# RelayOnAStick.net
KiCad netlist of a schematic drawn in EAGLE
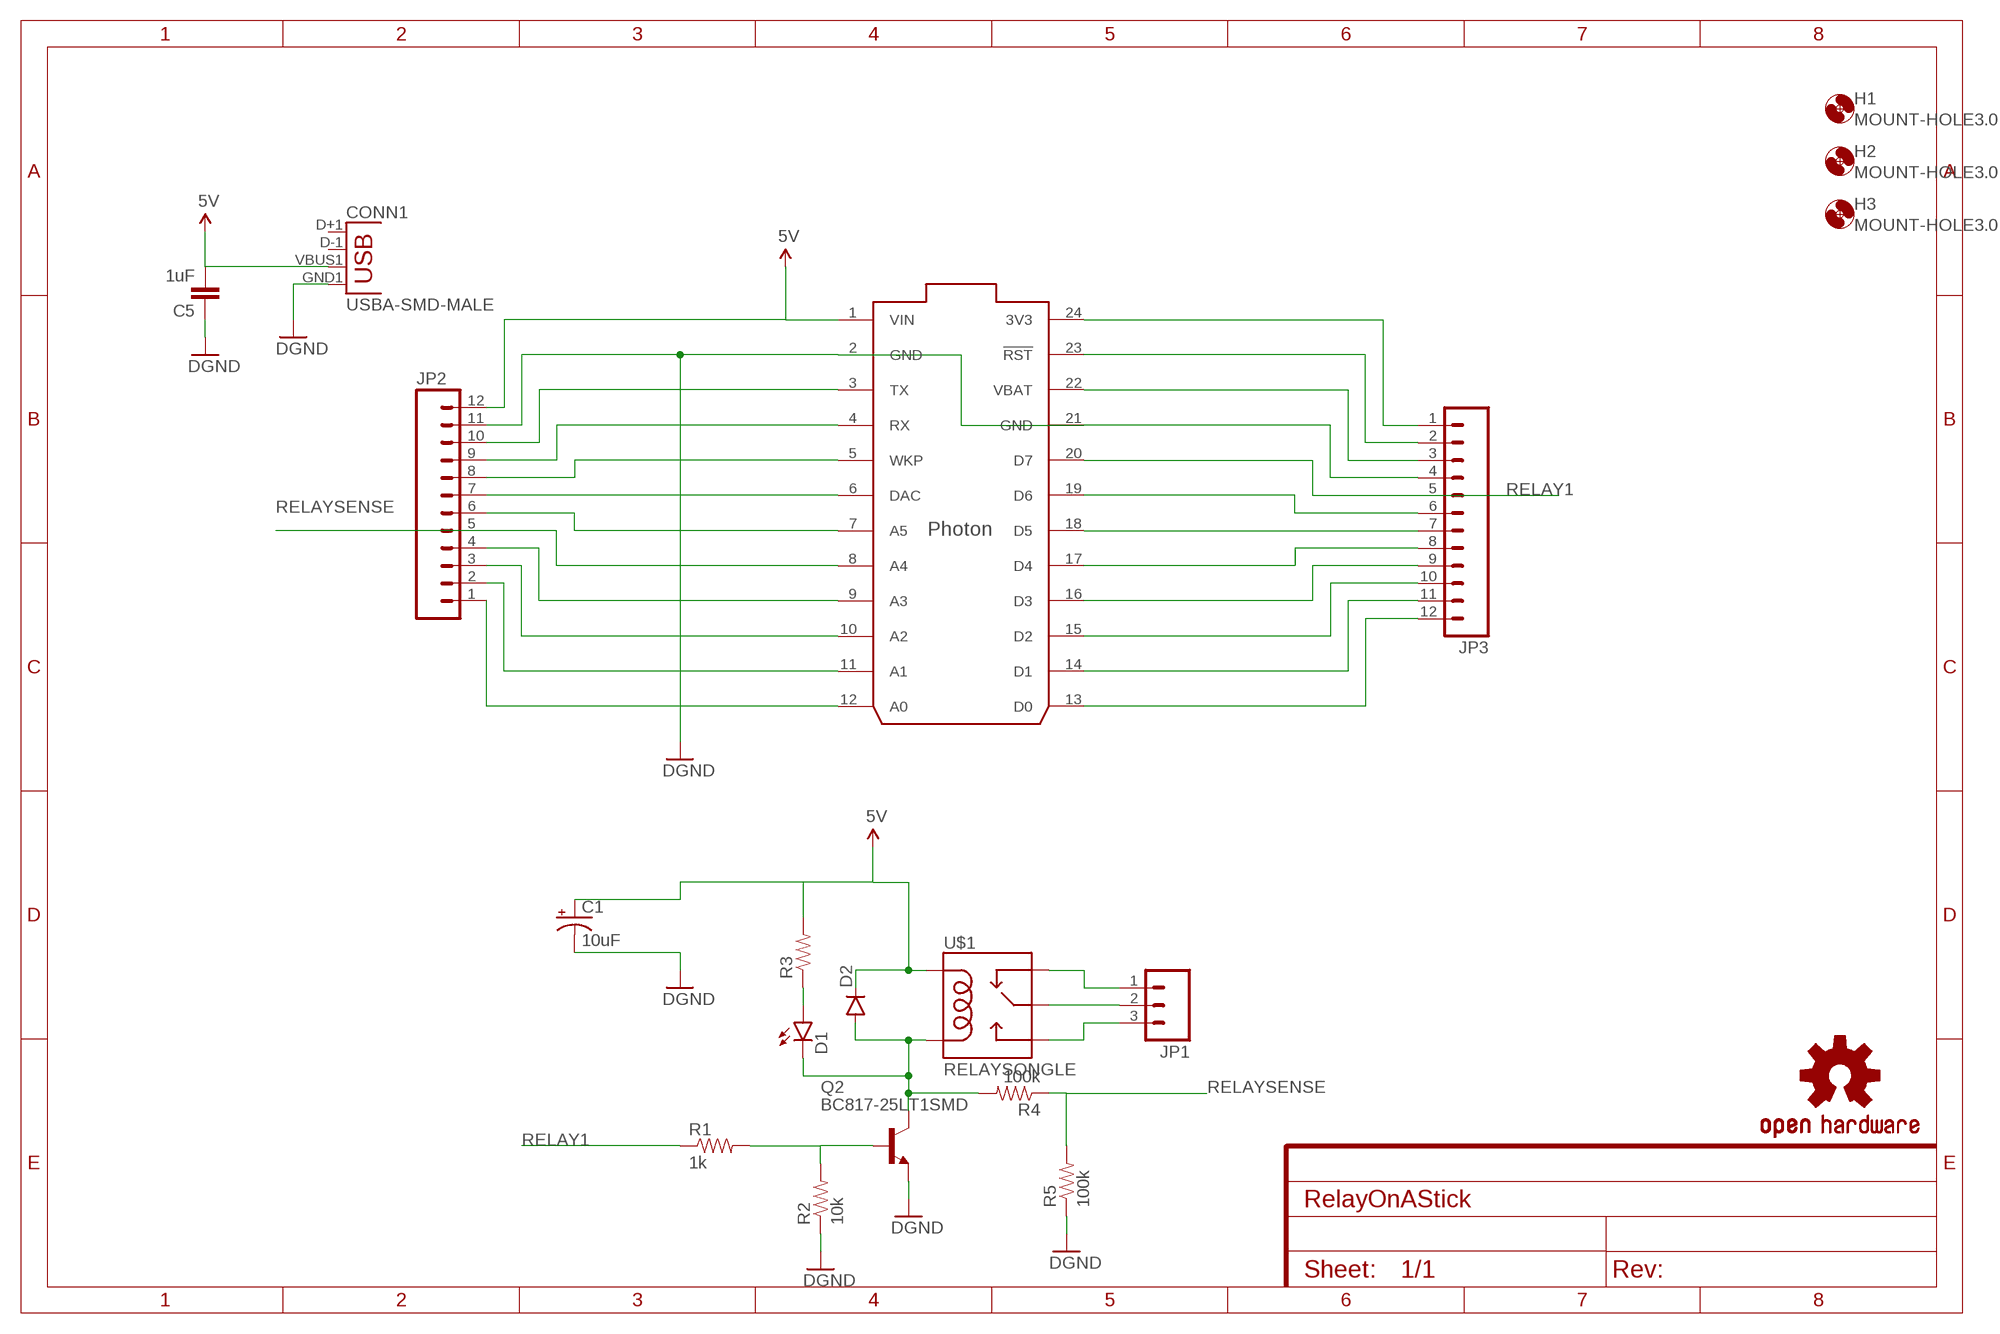
[diagram p0: schematic, sheet 1]

(export (version "E")
  (design (tool "Eeschema 10.0.6"))
  (components
    (comp (ref "C1")
      (value "10uF")
      (footprint "eagle-import:EIA3216")
      (libsource (lib "eagle-import") (part "10UF-16V-10%(TANT)"))
    )
    (comp (ref "C5")
      (value "1uF")
      (footprint "eagle-import:0805")
      (libsource (lib "eagle-import") (part "CAP0805"))
    )
    (comp (ref "CONN1")
      (value "USBA-SMD-MALE")
      (footprint "eagle-import:USB-A-SMT-MALE")
      (libsource (lib "eagle-import") (part "USBA-SMD-MALE"))
    )
    (comp (ref "D1")
      (value "LED1206")
      (footprint "eagle-import:LED-1206")
      (libsource (lib "eagle-import") (part "LED1206"))
    )
    (comp (ref "D2")
      (value "DIODESMA")
      (footprint "eagle-import:SMA-DIODE")
      (libsource (lib "eagle-import") (part "DIODESMA"))
    )
    (comp (ref "H1")
      (value "MOUNT-HOLE3.0")
      (footprint "eagle-import:3,0")
      (libsource (lib "eagle-import") (part "MOUNT-HOLE3.0"))
    )
    (comp (ref "H2")
      (value "MOUNT-HOLE3.0")
      (footprint "eagle-import:3,0")
      (libsource (lib "eagle-import") (part "MOUNT-HOLE3.0"))
    )
    (comp (ref "H3")
      (value "MOUNT-HOLE3.0")
      (footprint "eagle-import:3,0")
      (libsource (lib "eagle-import") (part "MOUNT-HOLE3.0"))
    )
    (comp (ref "IC1")
      (value "PHOTON")
      (footprint "eagle-import:PHOTON")
      (libsource (lib "eagle-import") (part "PHOTON_WITH_HEADERS"))
    )
    (comp (ref "JP1")
      (value "M03-SCREW-5MM")
      (footprint "eagle-import:SCREWTERMINAL-5MM-3")
      (libsource (lib "eagle-import") (part "M03-SCREW-5MM"))
    )
    (comp (ref "JP2")
      (value "M121X12_NO_SILK_KIT")
      (footprint "eagle-import:1X12_NO_SILK_KIT")
      (libsource (lib "eagle-import") (part "M121X12_NO_SILK_KIT"))
    )
    (comp (ref "JP3")
      (value "M121X12_NO_SILK_KIT")
      (footprint "eagle-import:1X12_NO_SILK_KIT")
      (libsource (lib "eagle-import") (part "M121X12_NO_SILK_KIT"))
    )
    (comp (ref "LOGO2")
      (value "OSHW-LOGOS")
      (footprint "eagle-import:OSHW-LOGO-S")
      (libsource (lib "eagle-import") (part "OSHW-LOGOS"))
    )
    (comp (ref "Q2")
      (value "BC817-25LT1SMD")
      (footprint "eagle-import:SOT23-BEC")
      (libsource (lib "eagle-import") (part "BC817SMD-25LT1"))
    )
    (comp (ref "R1")
      (value "1k")
      (footprint "eagle-import:1206")
      (libsource (lib "eagle-import") (part "RESISTOR1206"))
    )
    (comp (ref "R2")
      (value "10k")
      (footprint "eagle-import:1206")
      (libsource (lib "eagle-import") (part "RESISTOR1206"))
    )
    (comp (ref "R3")
      (value "RESISTOR1206")
      (footprint "eagle-import:1206")
      (libsource (lib "eagle-import") (part "RESISTOR1206"))
    )
    (comp (ref "R4")
      (value "100k")
      (footprint "eagle-import:1206")
      (libsource (lib "eagle-import") (part "RESISTOR1206"))
    )
    (comp (ref "R5")
      (value "100k")
      (footprint "eagle-import:1206")
      (libsource (lib "eagle-import") (part "RESISTOR1206"))
    )
    (comp (ref "U$1")
      (value "RELAYSONGLE")
      (footprint "eagle-import:SRD-5VDC-SL-C")
      (libsource (lib "eagle-import") (part "RELAYSONGLE"))
    )
  )
  (nets
    (net (code "1") (name "/RELAY1") (class "Default")
      (node (ref "IC1") (pin "20") (pinfunction "D7_20") (pintype "bidirectional"))
      (node (ref "JP3") (pin "5") (pinfunction "5_5") (pintype "passive"))
      (node (ref "R1") (pin "1") (pinfunction "1_1") (pintype "passive"))
    )
    (net (code "2") (name "/RELAYSENSE") (class "Default")
      (node (ref "IC1") (pin "8") (pinfunction "A4_8") (pintype "bidirectional"))
      (node (ref "JP2") (pin "5") (pinfunction "5_5") (pintype "passive"))
      (node (ref "R4") (pin "1") (pinfunction "1_1") (pintype "passive"))
      (node (ref "R5") (pin "2") (pinfunction "2_2") (pintype "passive"))
    )
    (net (code "3") (name "5V") (class "Default")
      (node (ref "C1") (pin "A") (pinfunction "+_A") (pintype "passive"))
      (node (ref "C5") (pin "2") (pinfunction "2_2") (pintype "passive"))
      (node (ref "CONN1") (pin "VBUS1") (pinfunction "VBUS_VBUS1") (pintype "bidirectional"))
      (node (ref "D2") (pin "C") (pinfunction "C_C") (pintype "passive"))
      (node (ref "IC1") (pin "1") (pinfunction "VIN_1") (pintype "power_in"))
      (node (ref "JP2") (pin "12") (pinfunction "12_12") (pintype "passive"))
      (node (ref "R3") (pin "2") (pinfunction "2_2") (pintype "passive"))
      (node (ref "U$1") (pin "COIL1") (pinfunction "COIL1_COIL1") (pintype "bidirectional"))
    )
    (net (code "4") (name "DGND") (class "Default")
      (node (ref "C1") (pin "C") (pinfunction "-_C") (pintype "passive"))
      (node (ref "C5") (pin "1") (pinfunction "1_1") (pintype "passive"))
      (node (ref "CONN1") (pin "GND1") (pinfunction "GND_GND1") (pintype "bidirectional"))
      (node (ref "IC1") (pin "2") (pinfunction "GND_2") (pintype "power_in"))
      (node (ref "IC1") (pin "21") (pinfunction "GND_21") (pintype "power_in"))
      (node (ref "JP2") (pin "11") (pinfunction "11_11") (pintype "passive"))
      (node (ref "JP3") (pin "4") (pinfunction "4_4") (pintype "passive"))
      (node (ref "Q2") (pin "E") (pinfunction "E_E") (pintype "passive"))
      (node (ref "R2") (pin "1") (pinfunction "1_1") (pintype "passive"))
      (node (ref "R5") (pin "1") (pinfunction "1_1") (pintype "passive"))
    )
    (net (code "5") (name "Net-(D1-PadA)") (class "Default")
      (node (ref "D1") (pin "A") (pinfunction "A_A") (pintype "passive"))
      (node (ref "R3") (pin "1") (pinfunction "1_1") (pintype "passive"))
    )
    (net (code "6") (name "Net-(D1-PadC)") (class "Default")
      (node (ref "D1") (pin "C") (pinfunction "C_C") (pintype "passive"))
      (node (ref "D2") (pin "A") (pinfunction "A_A") (pintype "passive"))
      (node (ref "Q2") (pin "C") (pinfunction "C_C") (pintype "passive"))
      (node (ref "R4") (pin "2") (pinfunction "2_2") (pintype "passive"))
      (node (ref "U$1") (pin "COIL2") (pinfunction "COIL2_COIL2") (pintype "bidirectional"))
    )
    (net (code "7") (name "Net-(IC1-3V3)") (class "Default")
      (node (ref "IC1") (pin "24") (pinfunction "3V3_24") (pintype "power_in"))
      (node (ref "JP3") (pin "1") (pinfunction "1_1") (pintype "passive"))
    )
    (net (code "8") (name "Net-(IC1-A0)") (class "Default")
      (node (ref "IC1") (pin "12") (pinfunction "A0_12") (pintype "bidirectional"))
      (node (ref "JP2") (pin "1") (pinfunction "1_1") (pintype "passive"))
    )
    (net (code "9") (name "Net-(IC1-A1)") (class "Default")
      (node (ref "IC1") (pin "11") (pinfunction "A1_11") (pintype "bidirectional"))
      (node (ref "JP2") (pin "2") (pinfunction "2_2") (pintype "passive"))
    )
    (net (code "10") (name "Net-(IC1-A2)") (class "Default")
      (node (ref "IC1") (pin "10") (pinfunction "A2_10") (pintype "bidirectional"))
      (node (ref "JP2") (pin "3") (pinfunction "3_3") (pintype "passive"))
    )
    (net (code "11") (name "Net-(IC1-A3)") (class "Default")
      (node (ref "IC1") (pin "9") (pinfunction "A3_9") (pintype "bidirectional"))
      (node (ref "JP2") (pin "4") (pinfunction "4_4") (pintype "passive"))
    )
    (net (code "12") (name "Net-(IC1-A5)") (class "Default")
      (node (ref "IC1") (pin "7") (pinfunction "A5_7") (pintype "bidirectional"))
      (node (ref "JP2") (pin "6") (pinfunction "6_6") (pintype "passive"))
    )
    (net (code "13") (name "Net-(IC1-D0)") (class "Default")
      (node (ref "IC1") (pin "13") (pinfunction "D0_13") (pintype "bidirectional"))
      (node (ref "JP3") (pin "12") (pinfunction "12_12") (pintype "passive"))
    )
    (net (code "14") (name "Net-(IC1-D1)") (class "Default")
      (node (ref "IC1") (pin "14") (pinfunction "D1_14") (pintype "bidirectional"))
      (node (ref "JP3") (pin "11") (pinfunction "11_11") (pintype "passive"))
    )
    (net (code "15") (name "Net-(IC1-D2)") (class "Default")
      (node (ref "IC1") (pin "15") (pinfunction "D2_15") (pintype "bidirectional"))
      (node (ref "JP3") (pin "10") (pinfunction "10_10") (pintype "passive"))
    )
    (net (code "16") (name "Net-(IC1-D3)") (class "Default")
      (node (ref "IC1") (pin "16") (pinfunction "D3_16") (pintype "bidirectional"))
      (node (ref "JP3") (pin "9") (pinfunction "9_9") (pintype "passive"))
    )
    (net (code "17") (name "Net-(IC1-D4)") (class "Default")
      (node (ref "IC1") (pin "17") (pinfunction "D4_17") (pintype "bidirectional"))
      (node (ref "JP3") (pin "8") (pinfunction "8_8") (pintype "passive"))
    )
    (net (code "18") (name "Net-(IC1-D5)") (class "Default")
      (node (ref "IC1") (pin "18") (pinfunction "D5_18") (pintype "bidirectional"))
      (node (ref "JP3") (pin "7") (pinfunction "7_7") (pintype "passive"))
    )
    (net (code "19") (name "Net-(IC1-D6)") (class "Default")
      (node (ref "IC1") (pin "19") (pinfunction "D6_19") (pintype "bidirectional"))
      (node (ref "JP3") (pin "6") (pinfunction "6_6") (pintype "passive"))
    )
    (net (code "20") (name "Net-(IC1-DAC)") (class "Default")
      (node (ref "IC1") (pin "6") (pinfunction "DAC_6") (pintype "bidirectional"))
      (node (ref "JP2") (pin "7") (pinfunction "7_7") (pintype "passive"))
    )
    (net (code "21") (name "Net-(IC1-RX)") (class "Default")
      (node (ref "IC1") (pin "4") (pinfunction "RX_4") (pintype "bidirectional"))
      (node (ref "JP2") (pin "9") (pinfunction "9_9") (pintype "passive"))
    )
    (net (code "22") (name "Net-(IC1-TX)") (class "Default")
      (node (ref "IC1") (pin "3") (pinfunction "TX_3") (pintype "bidirectional"))
      (node (ref "JP2") (pin "10") (pinfunction "10_10") (pintype "passive"))
    )
    (net (code "23") (name "Net-(IC1-VBAT)") (class "Default")
      (node (ref "IC1") (pin "22") (pinfunction "VBAT_22") (pintype "power_in"))
      (node (ref "JP3") (pin "3") (pinfunction "3_3") (pintype "passive"))
    )
    (net (code "24") (name "Net-(IC1-WKP)") (class "Default")
      (node (ref "IC1") (pin "5") (pinfunction "WKP_5") (pintype "bidirectional"))
      (node (ref "JP2") (pin "8") (pinfunction "8_8") (pintype "passive"))
    )
    (net (code "25") (name "Net-(IC1-~{RST})") (class "Default")
      (node (ref "IC1") (pin "23") (pinfunction "~{RST}_23") (pintype "bidirectional"))
      (node (ref "JP3") (pin "2") (pinfunction "2_2") (pintype "passive"))
    )
    (net (code "26") (name "Net-(Q2-PadB)") (class "Default")
      (node (ref "Q2") (pin "B") (pinfunction "B_B") (pintype "passive"))
      (node (ref "R1") (pin "2") (pinfunction "2_2") (pintype "passive"))
      (node (ref "R2") (pin "2") (pinfunction "2_2") (pintype "passive"))
    )
    (net (code "27") (name "Net-(U$1-MAIN)") (class "Default")
      (node (ref "JP1") (pin "2") (pinfunction "2_2") (pintype "passive"))
      (node (ref "U$1") (pin "COMMON") (pinfunction "MAIN_COMMON") (pintype "bidirectional"))
    )
    (net (code "28") (name "Net-(U$1-NC)") (class "Default")
      (node (ref "JP1") (pin "1") (pinfunction "1_1") (pintype "passive"))
      (node (ref "U$1") (pin "CLOSED") (pinfunction "NC_CLOSED") (pintype "bidirectional"))
    )
    (net (code "29") (name "Net-(U$1-NO)") (class "Default")
      (node (ref "JP1") (pin "3") (pinfunction "3_3") (pintype "passive"))
      (node (ref "U$1") (pin "OPEN") (pinfunction "NO_OPEN") (pintype "bidirectional"))
    )
    (net (code "30") (name "unconnected-(CONN1-D+-PadD+1)") (class "Default")
      (node (ref "CONN1") (pin "D+1") (pinfunction "D+_D+1") (pintype "bidirectional"))
    )
    (net (code "31") (name "unconnected-(CONN1-D--PadD-1)") (class "Default")
      (node (ref "CONN1") (pin "D-1") (pinfunction "D-_D-1") (pintype "bidirectional"))
    )
  )
)
